# TRACTIAN_Wireless.net
KiCad netlist of a schematic drawn in Altium Designer
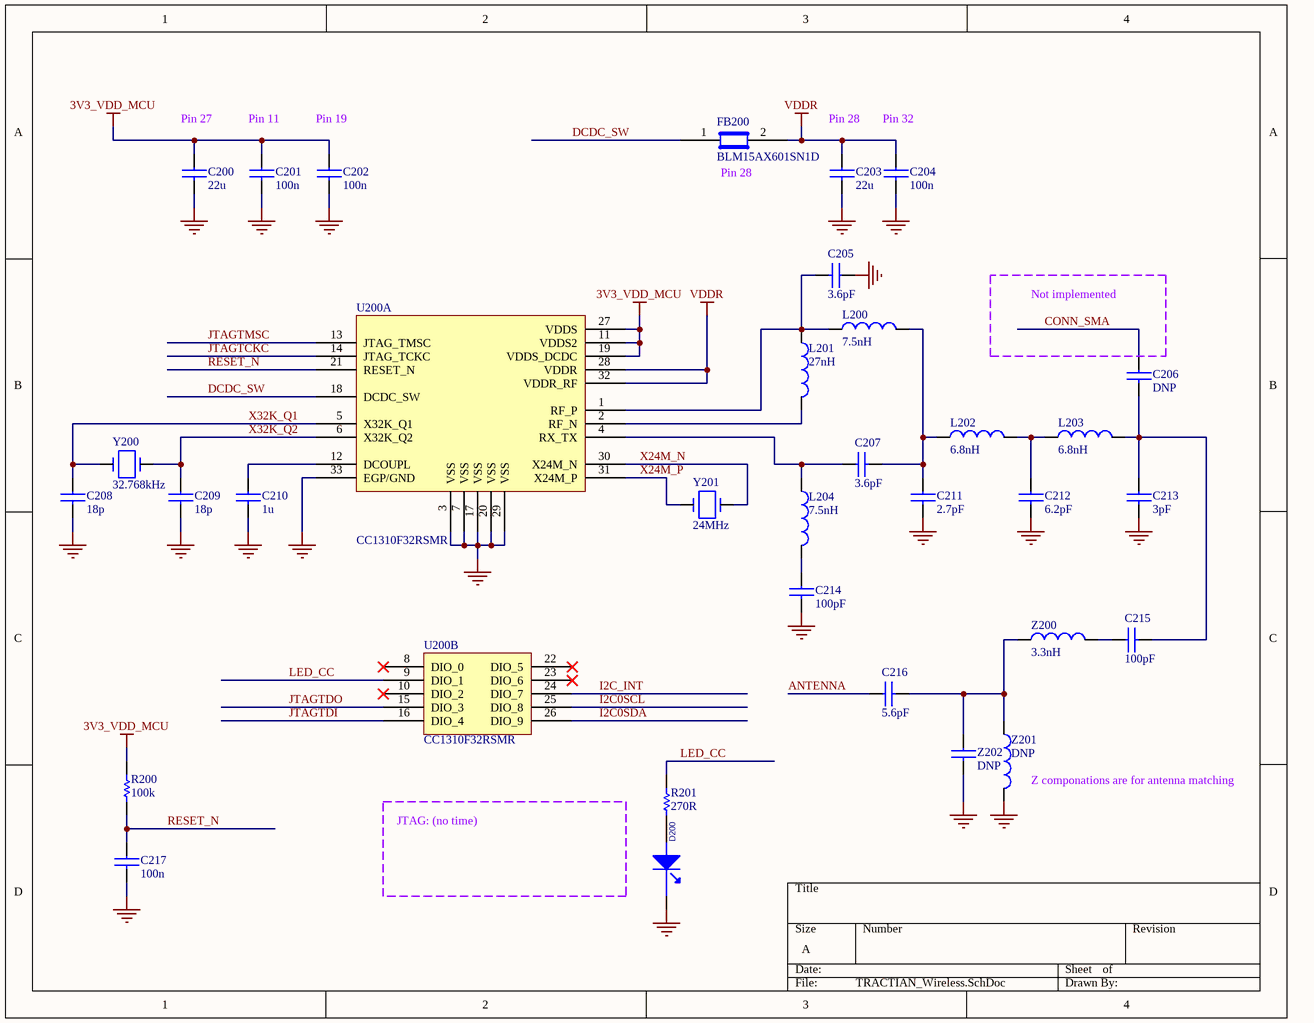
[diagram p0: TRACTIAN_Wireless.SchDoc]

(export (version "E")
  (design (tool "Eeschema 10.0.6"))
  (components
    (comp (ref "C200")
      (value "22u")
      (footprint "C0805")
      (description "CAP CER 22UF 16V 10% X5R 0805")
      (fields
        (field (name "MANUFACTURER") "TDK Corporation")
        (field (name "MANUFACTURER PART NUMBER") "C2012X5R1C226K")
        (field (name ".CHECKED PCB") "RF")
        (field (name ".CHECKED SCH") "RF")
      )
      (libsource (lib "TRACTIAN-HW-Challenge") (part "C2012X5R1C226K"))
    )
    (comp (ref "C201")
      (value "100n")
      (footprint "C0402")
      (description "CAP CER .10UF 50V X5R 10% 0402")
      (fields
        (field (name "MANUFACTURER") "TDK Corporation")
        (field (name "MANUFACTURER PART NUMBER") "C1005X5R1H104K")
      )
      (libsource (lib "TRACTIAN-HW-Challenge") (part "C1005X5R1H104K"))
    )
    (comp (ref "C202")
      (value "100n")
      (footprint "C0402")
      (description "CAP CER .10UF 50V X5R 10% 0402")
      (fields
        (field (name "MANUFACTURER") "TDK Corporation")
        (field (name "MANUFACTURER PART NUMBER") "C1005X5R1H104K")
      )
      (libsource (lib "TRACTIAN-HW-Challenge") (part "C1005X5R1H104K"))
    )
    (comp (ref "C203")
      (value "22u")
      (footprint "C0805")
      (description "CAP CER 22UF 16V 10% X5R 0805")
      (fields
        (field (name "MANUFACTURER") "TDK Corporation")
        (field (name "MANUFACTURER PART NUMBER") "C2012X5R1C226K")
        (field (name ".CHECKED PCB") "RF")
        (field (name ".CHECKED SCH") "RF")
      )
      (libsource (lib "TRACTIAN-HW-Challenge") (part "C2012X5R1C226K"))
    )
    (comp (ref "C204")
      (value "100n")
      (footprint "C0402")
      (description "CAP CER .10UF 50V X5R 10% 0402")
      (fields
        (field (name "MANUFACTURER") "TDK Corporation")
        (field (name "MANUFACTURER PART NUMBER") "C1005X5R1H104K")
      )
      (libsource (lib "TRACTIAN-HW-Challenge") (part "C1005X5R1H104K"))
    )
    (comp (ref "C205")
      (value "3.6pF")
      (footprint "C0402")
      (description "CAPACITOR")
      (libsource (lib "TRACTIAN-HW-Challenge") (part "Cap"))
    )
    (comp (ref "C206")
      (value "DNP")
      (footprint "C0402")
      (description "CAPACITOR")
      (libsource (lib "TRACTIAN-HW-Challenge") (part "Cap"))
    )
    (comp (ref "C207")
      (value "3.6pF")
      (footprint "C0402")
      (description "CAPACITOR")
      (libsource (lib "TRACTIAN-HW-Challenge") (part "Cap"))
    )
    (comp (ref "C208")
      (value "18p")
      (footprint "C0402")
      (description "CAP CER 18PF 50V C0G 5% 0402")
      (fields
        (field (name "MANUFACTURER") "TDK Corporation")
        (field (name "MANUFACTURER PART NUMBER") "C1005C0G1H180J")
      )
      (libsource (lib "Integrated_Library_RF_FEB_2012") (part "C1005C0G1H180J"))
    )
    (comp (ref "C209")
      (value "18p")
      (footprint "C0402")
      (description "CAP CER 18PF 50V C0G 5% 0402")
      (fields
        (field (name "MANUFACTURER") "TDK Corporation")
        (field (name "MANUFACTURER PART NUMBER") "C1005C0G1H180J")
      )
      (libsource (lib "Integrated_Library_RF_FEB_2012") (part "C1005C0G1H180J"))
    )
    (comp (ref "C210")
      (value "1u")
      (footprint "C0402")
      (description "CAP CER 1.0UF 16V X5R 0402")
      (fields
        (field (name "MANUFACTURER") "TDK Corporation")
        (field (name "MANUFACTURER PART NUMBER") "C1005X5R1C105K")
      )
      (libsource (lib "TRACTIAN-HW-Challenge") (part "C1005X5R1C105K"))
    )
    (comp (ref "C211")
      (value "2.7pF")
      (footprint "C0402")
      (description "CAPACITOR")
      (libsource (lib "TRACTIAN-HW-Challenge") (part "Cap"))
    )
    (comp (ref "C212")
      (value "6.2pF")
      (footprint "C0402")
      (description "CAPACITOR")
      (libsource (lib "TRACTIAN-HW-Challenge") (part "Cap"))
    )
    (comp (ref "C213")
      (value "3pF")
      (footprint "C0402")
      (description "CAPACITOR")
      (libsource (lib "TRACTIAN-HW-Challenge") (part "Cap"))
    )
    (comp (ref "C214")
      (value "100pF")
      (footprint "C0402")
      (description "CAPACITOR")
      (libsource (lib "TRACTIAN-HW-Challenge") (part "Cap"))
    )
    (comp (ref "C215")
      (value "100pF")
      (footprint "C0402")
      (description "CAPACITOR")
      (libsource (lib "TRACTIAN-HW-Challenge") (part "Cap"))
    )
    (comp (ref "C216")
      (value "5.6pF")
      (footprint "C0402")
      (description "CAPACITOR")
      (libsource (lib "TRACTIAN-HW-Challenge") (part "Cap"))
    )
    (comp (ref "C217")
      (value "100n")
      (footprint "C0402")
      (description "CAP CER .10UF 50V X5R 10% 0402")
      (fields
        (field (name "MANUFACTURER") "TDK Corporation")
        (field (name "MANUFACTURER PART NUMBER") "C1005X5R1H104K")
      )
      (libsource (lib "TRACTIAN-HW-Challenge") (part "C1005X5R1H104K"))
    )
    (comp (ref "D200")
      (value "~")
      (footprint "LED_0603")
      (description "Generic LED 0603")
      (libsource (lib "TRACTIAN-HW-Challenge") (part "LED"))
    )
    (comp (ref "FB200")
      (value "BLM15AX601SN1D")
      (footprint "C0402")
      (description "FERRITE CHIP 600 OHM 0402 420mA")
      (fields (field (name "MANUFACTURER") "Murata Electronics North America"))
      (libsource (lib "TRACTIAN-HW-Challenge") (part "BLM15AX601SN1D"))
    )
    (comp (ref "L200")
      (value "7.5nH")
      (footprint "L0402")
      (description "INDUCTOR")
      (libsource (lib "TRACTIAN-HW-Challenge") (part "Ind"))
    )
    (comp (ref "L201")
      (value "27nH")
      (footprint "L0402")
      (description "INDUCTOR")
      (libsource (lib "TRACTIAN-HW-Challenge") (part "Ind"))
    )
    (comp (ref "L202")
      (value "6.8nH")
      (footprint "L0402")
      (description "INDUCTOR")
      (libsource (lib "TRACTIAN-HW-Challenge") (part "Ind"))
    )
    (comp (ref "L203")
      (value "6.8nH")
      (footprint "L0402")
      (description "INDUCTOR")
      (libsource (lib "TRACTIAN-HW-Challenge") (part "Ind"))
    )
    (comp (ref "L204")
      (value "7.5nH")
      (footprint "L0402")
      (description "INDUCTOR")
      (libsource (lib "TRACTIAN-HW-Challenge") (part "Ind"))
    )
    (comp (ref "R200")
      (value "100k")
      (footprint "R0402")
      (description "RES 100K OHM 1/16W 1% 0402 SMD")
      (fields
        (field (name "MANUFACTURER") "Stackpole Electronics Inc")
        (field (name "MANUFACTURER PART NUMBER") "RMCF0402FT100K")
      )
      (libsource (lib "TRACTIAN-HW-Challenge") (part "RMCF0402FT100K"))
    )
    (comp (ref "R201")
      (value "270R")
      (footprint "R0402")
      (description "Generic resistor")
      (libsource (lib "TRACTIAN-HW-Challenge") (part "Res"))
    )
    (comp (ref "U200")
      (value "CC1310F32RSMR")
      (footprint "VQFN-32")
      (description "CC1310 SimpleLink™ Ultra-Low-Power Sub-1 GHz Wireless MCU")
      (libsource (lib "TRACTIAN-HW-Challenge") (part "CC1310F32RSMR"))
    )
    (comp (ref "Y200")
      (value "32.768kHz")
      (footprint "ABS06")
      (description "CRYSTAL 32.768 KHZ 9.0 PF SMD")
      (fields
        (field (name "MANUFACTURER") "Abracon Corporation")
        (field (name "MANUFACTURER PART NUMBER") "ABS06-32.768KHZ-9-1-T")
      )
      (libsource (lib "TRACTIAN-HW-Challenge") (part "ABS06-32.768KHZ-9-1-T"))
    )
    (comp (ref "Y201")
      (value "24MHz")
      (footprint "ABS06")
      (description "CRYSTAL 24.0000MHZ 18PF SMD")
      (fields
        (field (name "MANUFACTURER") "Abracon Corporation")
        (field (name "MANUFACTURER PART NUMBER") "ABM7-24.000MHZ-D-2-Y-T")
        (field (name ".CREATOR") "MM")
        (field (name ".CHECKED PCB") "RF, used by MM")
        (field (name ".CHECKED SCH") "MM, checked by RF")
      )
      (libsource (lib "TRACTIAN-HW-Challenge") (part "ABM7-24.000MHZ-D-2-Y-T"))
    )
    (comp (ref "Z200")
      (value "3.3nH")
      (footprint "L0402")
      (description "INDUCTOR")
      (libsource (lib "TRACTIAN-HW-Challenge") (part "Ind"))
    )
    (comp (ref "Z201")
      (value "DNP")
      (footprint "L0402")
      (description "INDUCTOR")
      (libsource (lib "TRACTIAN-HW-Challenge") (part "Ind"))
    )
    (comp (ref "Z202")
      (value "DNP")
      (footprint "C0402")
      (description "CAPACITOR")
      (libsource (lib "TRACTIAN-HW-Challenge") (part "Cap"))
    )
  )
  (nets
    (net (code "1") (name "/ANTENNA") (class "Default")
      (node (ref "C216") (pin "1") (pinfunction "1_1") (pintype "passive"))
    )
    (net (code "2") (name "/CONN_SMA") (class "Default")
      (node (ref "C206") (pin "1") (pinfunction "1_1") (pintype "passive"))
    )
    (net (code "3") (name "/DCDC_SW") (class "Default")
      (node (ref "FB200") (pin "1") (pinfunction "1_1") (pintype "passive"))
      (node (ref "U200") (pin "18") (pinfunction "DCDC_SW_18") (pintype "passive"))
    )
    (net (code "4") (name "/I2C0SCL") (class "Default")
      (node (ref "U200") (pin "25") (pinfunction "DIO_8_25") (pintype "passive"))
    )
    (net (code "5") (name "/I2C0SDA") (class "Default")
      (node (ref "U200") (pin "26") (pinfunction "DIO_9_26") (pintype "passive"))
    )
    (net (code "6") (name "/I2C_INT") (class "Default")
      (node (ref "U200") (pin "24") (pinfunction "DIO_7_24") (pintype "passive"))
    )
    (net (code "7") (name "/JTAGTCKC") (class "Default")
      (node (ref "U200") (pin "14") (pinfunction "JTAG_TCKC_14") (pintype "passive"))
    )
    (net (code "8") (name "/JTAGTDI") (class "Default")
      (node (ref "U200") (pin "16") (pinfunction "DIO_4_16") (pintype "passive"))
    )
    (net (code "9") (name "/JTAGTDO") (class "Default")
      (node (ref "U200") (pin "15") (pinfunction "DIO_3_15") (pintype "passive"))
    )
    (net (code "10") (name "/JTAGTMSC") (class "Default")
      (node (ref "U200") (pin "13") (pinfunction "JTAG_TMSC_13") (pintype "passive"))
    )
    (net (code "11") (name "/LED_CC") (class "Default")
      (node (ref "R201") (pin "2") (pinfunction "2_2") (pintype "passive"))
      (node (ref "U200") (pin "9") (pinfunction "DIO_1_9") (pintype "passive"))
    )
    (net (code "12") (name "/RESET_N") (class "Default")
      (node (ref "C217") (pin "1") (pinfunction "1_1") (pintype "passive"))
      (node (ref "R200") (pin "1") (pinfunction "1_1") (pintype "passive"))
      (node (ref "U200") (pin "21") (pinfunction "RESET_N_21") (pintype "passive"))
    )
    (net (code "13") (name "/X24M_N") (class "Default")
      (node (ref "U200") (pin "30") (pinfunction "X24M_N_30") (pintype "passive"))
      (node (ref "Y201") (pin "2") (pinfunction "2_2") (pintype "passive"))
    )
    (net (code "14") (name "/X24M_P") (class "Default")
      (node (ref "U200") (pin "31") (pinfunction "X24M_P_31") (pintype "passive"))
      (node (ref "Y201") (pin "1") (pinfunction "1_1") (pintype "passive"))
    )
    (net (code "15") (name "/X32K_Q1") (class "Default")
      (node (ref "C208") (pin "1") (pinfunction "1_1") (pintype "passive"))
      (node (ref "U200") (pin "5") (pinfunction "X32K_Q1_5") (pintype "passive"))
      (node (ref "Y200") (pin "1") (pinfunction "1_1") (pintype "passive"))
    )
    (net (code "16") (name "/X32K_Q2") (class "Default")
      (node (ref "C209") (pin "1") (pinfunction "1_1") (pintype "passive"))
      (node (ref "U200") (pin "6") (pinfunction "X32K_Q2_6") (pintype "passive"))
      (node (ref "Y200") (pin "2") (pinfunction "2_2") (pintype "passive"))
    )
    (net (code "17") (name "3V3_VDD_MCU") (class "Default")
      (node (ref "C200") (pin "1") (pinfunction "1_1") (pintype "passive"))
      (node (ref "C201") (pin "1") (pinfunction "1_1") (pintype "passive"))
      (node (ref "C202") (pin "1") (pinfunction "1_1") (pintype "passive"))
      (node (ref "R200") (pin "2") (pinfunction "2_2") (pintype "passive"))
      (node (ref "U200") (pin "11") (pinfunction "VDDS2_11") (pintype "passive"))
      (node (ref "U200") (pin "19") (pinfunction "VDDS_DCDC_19") (pintype "passive"))
      (node (ref "U200") (pin "27") (pinfunction "VDDS_27") (pintype "passive"))
    )
    (net (code "18") (name "GND") (class "Default")
      (node (ref "C200") (pin "2") (pinfunction "2_2") (pintype "passive"))
      (node (ref "C201") (pin "2") (pinfunction "2_2") (pintype "passive"))
      (node (ref "C202") (pin "2") (pinfunction "2_2") (pintype "passive"))
      (node (ref "C203") (pin "2") (pinfunction "2_2") (pintype "passive"))
      (node (ref "C204") (pin "2") (pinfunction "2_2") (pintype "passive"))
      (node (ref "C205") (pin "1") (pinfunction "1_1") (pintype "passive"))
      (node (ref "C208") (pin "2") (pinfunction "2_2") (pintype "passive"))
      (node (ref "C209") (pin "2") (pinfunction "2_2") (pintype "passive"))
      (node (ref "C210") (pin "2") (pinfunction "2_2") (pintype "passive"))
      (node (ref "C211") (pin "2") (pinfunction "2_2") (pintype "passive"))
      (node (ref "C212") (pin "2") (pinfunction "2_2") (pintype "passive"))
      (node (ref "C213") (pin "2") (pinfunction "2_2") (pintype "passive"))
      (node (ref "C214") (pin "2") (pinfunction "2_2") (pintype "passive"))
      (node (ref "C217") (pin "2") (pinfunction "2_2") (pintype "passive"))
      (node (ref "D200") (pin "1") (pinfunction "cathode_1") (pintype "passive"))
      (node (ref "U200") (pin "17") (pinfunction "VSS_17") (pintype "passive"))
      (node (ref "U200") (pin "20") (pinfunction "VSS_20") (pintype "passive"))
      (node (ref "U200") (pin "29") (pinfunction "VSS_29") (pintype "passive"))
      (node (ref "U200") (pin "3") (pinfunction "VSS_3") (pintype "passive"))
      (node (ref "U200") (pin "33") (pinfunction "EGP/GND_33") (pintype "passive"))
      (node (ref "U200") (pin "7") (pinfunction "VSS_7") (pintype "passive"))
      (node (ref "Z201") (pin "2") (pinfunction "2_2") (pintype "passive"))
      (node (ref "Z202") (pin "2") (pinfunction "2_2") (pintype "passive"))
    )
    (net (code "19") (name "Net-(C206-Pad2)") (class "Default")
      (node (ref "C206") (pin "2") (pinfunction "2_2") (pintype "passive"))
      (node (ref "C213") (pin "1") (pinfunction "1_1") (pintype "passive"))
      (node (ref "C215") (pin "2") (pinfunction "2_2") (pintype "passive"))
      (node (ref "L203") (pin "2") (pinfunction "2_2") (pintype "passive"))
    )
    (net (code "20") (name "Net-(C207-Pad2)") (class "Default")
      (node (ref "C207") (pin "2") (pinfunction "2_2") (pintype "passive"))
      (node (ref "C211") (pin "1") (pinfunction "1_1") (pintype "passive"))
      (node (ref "L200") (pin "2") (pinfunction "2_2") (pintype "passive"))
      (node (ref "L202") (pin "1") (pinfunction "1_1") (pintype "passive"))
    )
    (net (code "21") (name "Net-(C212-Pad1)") (class "Default")
      (node (ref "C212") (pin "1") (pinfunction "1_1") (pintype "passive"))
      (node (ref "L202") (pin "2") (pinfunction "2_2") (pintype "passive"))
      (node (ref "L203") (pin "1") (pinfunction "1_1") (pintype "passive"))
    )
    (net (code "22") (name "Net-(C214-Pad1)") (class "Default")
      (node (ref "C214") (pin "1") (pinfunction "1_1") (pintype "passive"))
      (node (ref "L204") (pin "2") (pinfunction "2_2") (pintype "passive"))
    )
    (net (code "23") (name "Net-(C215-Pad1)") (class "Default")
      (node (ref "C215") (pin "1") (pinfunction "1_1") (pintype "passive"))
      (node (ref "Z200") (pin "2") (pinfunction "2_2") (pintype "passive"))
    )
    (net (code "24") (name "Net-(C216-Pad2)") (class "Default")
      (node (ref "C216") (pin "2") (pinfunction "2_2") (pintype "passive"))
      (node (ref "Z200") (pin "1") (pinfunction "1_1") (pintype "passive"))
      (node (ref "Z201") (pin "1") (pinfunction "1_1") (pintype "passive"))
      (node (ref "Z202") (pin "1") (pinfunction "1_1") (pintype "passive"))
    )
    (net (code "25") (name "Net-(D200-ANODE)") (class "Default")
      (node (ref "D200") (pin "2") (pinfunction "ANODE_2") (pintype "passive"))
      (node (ref "R201") (pin "1") (pinfunction "1_1") (pintype "passive"))
    )
    (net (code "26") (name "Net-(U200A-DCOUPL)") (class "Default")
      (node (ref "C210") (pin "1") (pinfunction "1_1") (pintype "passive"))
      (node (ref "U200") (pin "12") (pinfunction "DCOUPL_12") (pintype "passive"))
    )
    (net (code "27") (name "Net-(U200A-RF_N)") (class "Default")
      (node (ref "L201") (pin "2") (pinfunction "2_2") (pintype "passive"))
      (node (ref "U200") (pin "2") (pinfunction "RF_N_2") (pintype "passive"))
    )
    (net (code "28") (name "Net-(U200A-RF_P)") (class "Default")
      (node (ref "C205") (pin "2") (pinfunction "2_2") (pintype "passive"))
      (node (ref "L200") (pin "1") (pinfunction "1_1") (pintype "passive"))
      (node (ref "L201") (pin "1") (pinfunction "1_1") (pintype "passive"))
      (node (ref "U200") (pin "1") (pinfunction "RF_P_1") (pintype "passive"))
    )
    (net (code "29") (name "Net-(U200A-RX_TX)") (class "Default")
      (node (ref "C207") (pin "1") (pinfunction "1_1") (pintype "passive"))
      (node (ref "L204") (pin "1") (pinfunction "1_1") (pintype "passive"))
      (node (ref "U200") (pin "4") (pinfunction "RX_TX_4") (pintype "passive"))
    )
    (net (code "30") (name "VDDR") (class "Default")
      (node (ref "C203") (pin "1") (pinfunction "1_1") (pintype "passive"))
      (node (ref "C204") (pin "1") (pinfunction "1_1") (pintype "passive"))
      (node (ref "FB200") (pin "2") (pinfunction "2_2") (pintype "passive"))
      (node (ref "U200") (pin "28") (pinfunction "VDDR_28") (pintype "passive"))
      (node (ref "U200") (pin "32") (pinfunction "VDDR_RF_32") (pintype "passive"))
    )
    (net (code "31") (name "unconnected-(U200B-DIO_0-Pad8)") (class "Default")
      (node (ref "U200") (pin "8") (pinfunction "DIO_0_8") (pintype "passive+no_connect"))
    )
    (net (code "32") (name "unconnected-(U200B-DIO_2-Pad10)") (class "Default")
      (node (ref "U200") (pin "10") (pinfunction "DIO_2_10") (pintype "passive+no_connect"))
    )
    (net (code "33") (name "unconnected-(U200B-DIO_5-Pad22)") (class "Default")
      (node (ref "U200") (pin "22") (pinfunction "DIO_5_22") (pintype "passive+no_connect"))
    )
    (net (code "34") (name "unconnected-(U200B-DIO_6-Pad23)") (class "Default")
      (node (ref "U200") (pin "23") (pinfunction "DIO_6_23") (pintype "passive+no_connect"))
    )
  )
)
